# QL_keyboard.net
KiCad netlist of a schematic drawn in EAGLE
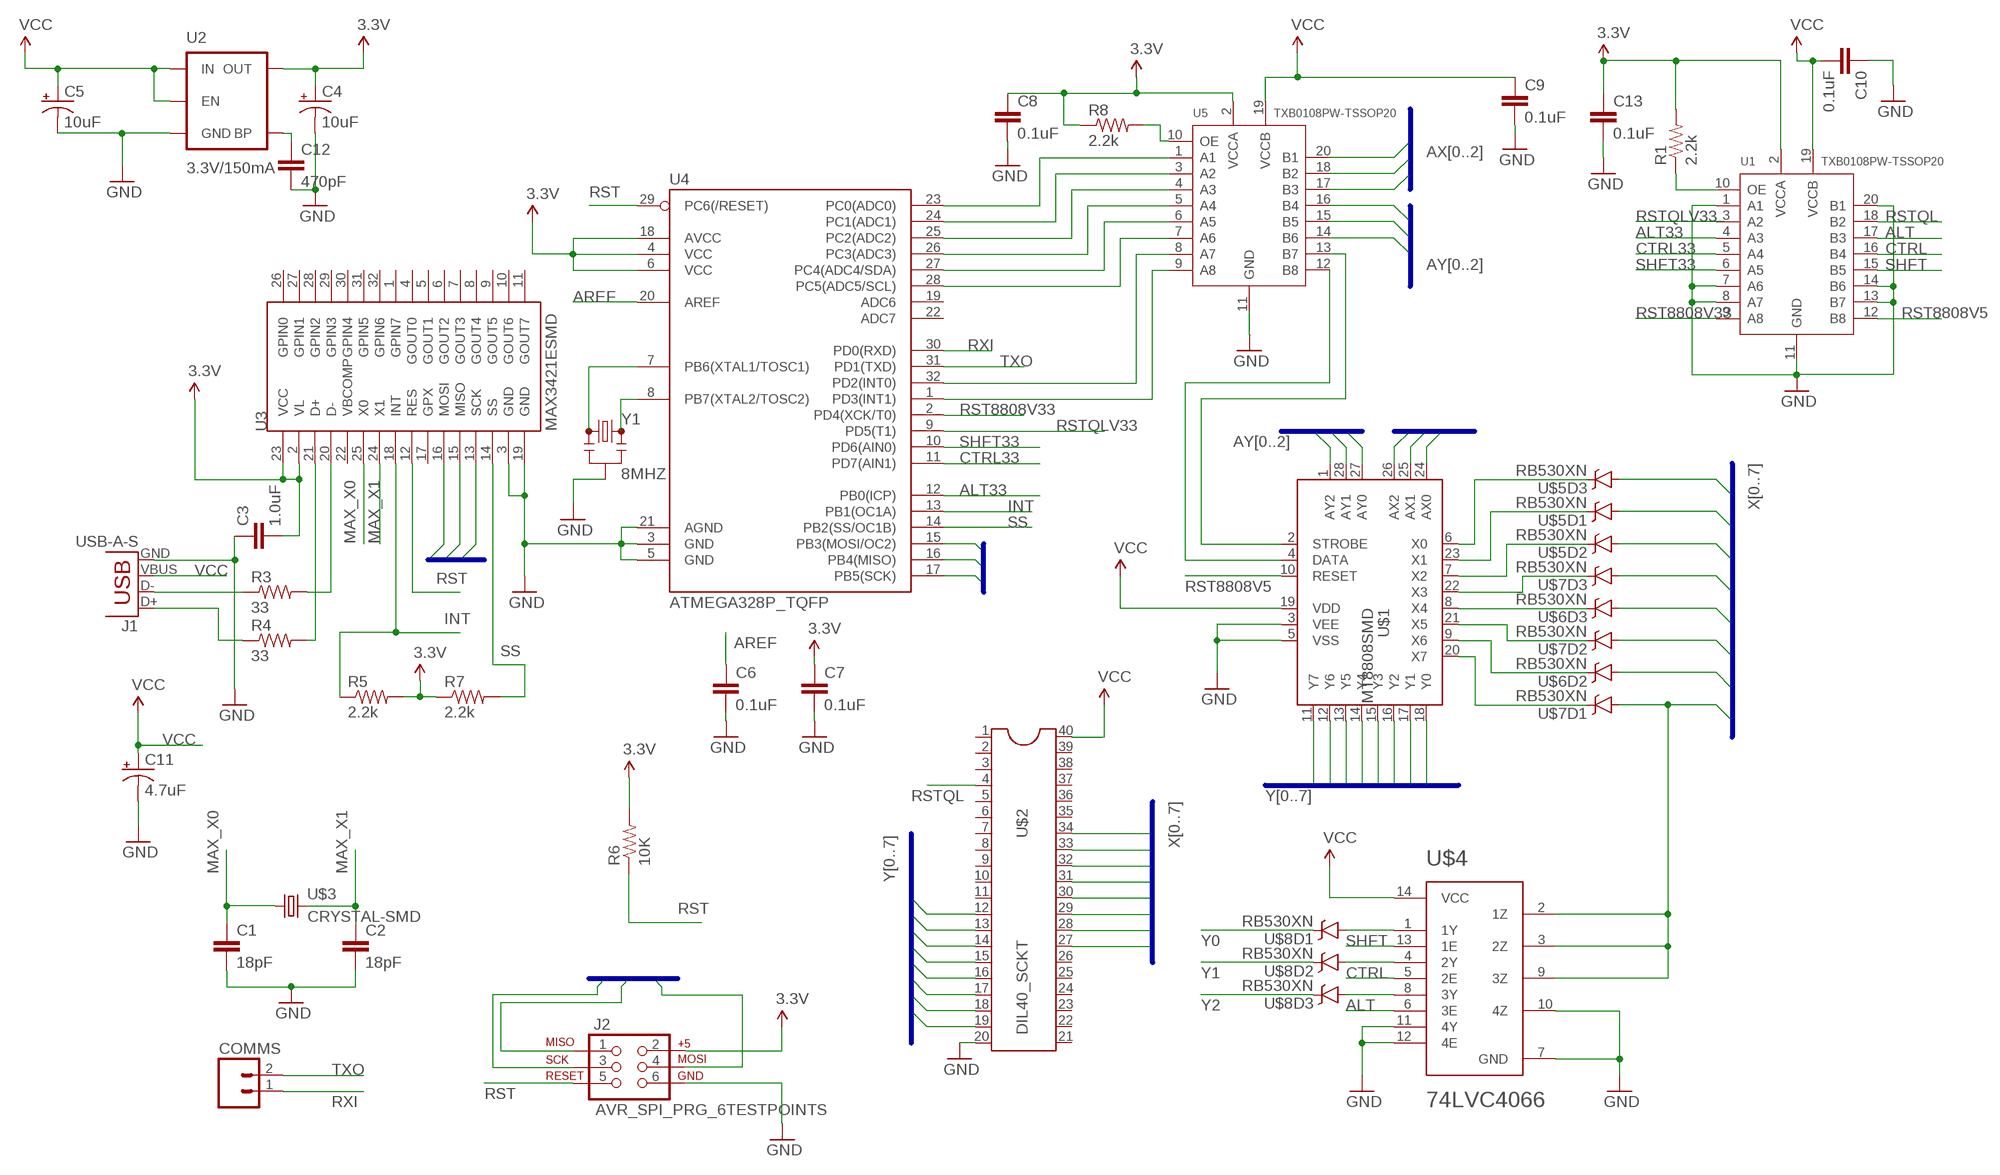
[diagram p0: schematic, sheet 1]

(export (version "E")
  (design (tool "Eeschema 10.0.6"))
  (components
    (comp (ref "C1")
      (value "18pF")
      (footprint "eagle-import:0603-CAP")
      (libsource (lib "eagle-import") (part "CAP0603-CAP"))
    )
    (comp (ref "C2")
      (value "18pF")
      (footprint "eagle-import:0603-CAP")
      (libsource (lib "eagle-import") (part "CAP0603-CAP"))
    )
    (comp (ref "C3")
      (value "1.0uF")
      (footprint "eagle-import:0603-CAP")
      (libsource (lib "eagle-import") (part "1.0UF-16V-10%(0603)"))
    )
    (comp (ref "C4")
      (value "10uF")
      (footprint "eagle-import:EIA3216")
      (libsource (lib "eagle-import") (part "10UF-16V-10%(TANT)"))
    )
    (comp (ref "C5")
      (value "10uF")
      (footprint "eagle-import:EIA3216")
      (libsource (lib "eagle-import") (part "10UF-16V-10%(TANT)"))
    )
    (comp (ref "C6")
      (value "0.1uF")
      (footprint "eagle-import:0603-CAP")
      (libsource (lib "eagle-import") (part "2.2UF-10V-20%(0603)"))
    )
    (comp (ref "C7")
      (value "0.1uF")
      (footprint "eagle-import:0603-CAP")
      (libsource (lib "eagle-import") (part "2.2UF-10V-20%(0603)"))
    )
    (comp (ref "C8")
      (value "0.1uF")
      (footprint "eagle-import:0603-CAP")
      (libsource (lib "eagle-import") (part "2.2UF-10V-20%(0603)"))
    )
    (comp (ref "C9")
      (value "0.1uF")
      (footprint "eagle-import:0603-CAP")
      (libsource (lib "eagle-import") (part "2.2UF-10V-20%(0603)"))
    )
    (comp (ref "C10")
      (value "0.1uF")
      (footprint "eagle-import:0603-CAP")
      (libsource (lib "eagle-import") (part "2.2UF-10V-20%(0603)"))
    )
    (comp (ref "C11")
      (value "4.7uF")
      (footprint "eagle-import:0603-POL")
      (libsource (lib "eagle-import") (part "10UF-6.3V-20%(0603)(TANT){dblquote}"))
    )
    (comp (ref "C12")
      (value "470pF")
      (footprint "eagle-import:0603-CAP")
      (libsource (lib "eagle-import") (part "2.2UF-10V-20%(0603)"))
    )
    (comp (ref "C13")
      (value "0.1uF")
      (footprint "eagle-import:0603-CAP")
      (libsource (lib "eagle-import") (part "2.2UF-10V-20%(0603)"))
    )
    (comp (ref "COMMS")
      (value "M02PTH")
      (footprint "eagle-import:1X02")
      (libsource (lib "eagle-import") (part "M02PTH"))
    )
    (comp (ref "J1")
      (value "USB-A-S")
      (footprint "eagle-import:USB-A-S")
      (libsource (lib "eagle-import") (part "USB-A-S"))
    )
    (comp (ref "J2")
      (value "AVR_SPI_PRG_6TESTPOINTS")
      (footprint "eagle-import:2X3_TEST_POINTS")
      (libsource (lib "eagle-import") (part "AVR_SPI_PRG_6TESTPOINTS"))
    )
    (comp (ref "R1")
      (value "2.2k")
      (footprint "eagle-import:0603-RES")
      (libsource (lib "eagle-import") (part "2.2KOHM-1/10W-1%(0603)"))
    )
    (comp (ref "R3")
      (value "33")
      (footprint "eagle-import:0603-RES")
      (libsource (lib "eagle-import") (part "33OHM1/10W1%(0603)"))
    )
    (comp (ref "R4")
      (value "33")
      (footprint "eagle-import:0603-RES")
      (libsource (lib "eagle-import") (part "33OHM1/10W1%(0603)"))
    )
    (comp (ref "R5")
      (value "2.2k")
      (footprint "eagle-import:0603-RES")
      (libsource (lib "eagle-import") (part "2.2KOHM-1/10W-1%(0603)"))
    )
    (comp (ref "R6")
      (value "10K")
      (footprint "eagle-import:0603-RES")
      (libsource (lib "eagle-import") (part "10KOHM-1/10W-1%(0603)0603"))
    )
    (comp (ref "R7")
      (value "2.2k")
      (footprint "eagle-import:0603-RES")
      (libsource (lib "eagle-import") (part "2.2KOHM-1/10W-1%(0603)"))
    )
    (comp (ref "R8")
      (value "2.2k")
      (footprint "eagle-import:0603-RES")
      (libsource (lib "eagle-import") (part "2.2KOHM-1/10W-1%(0603)"))
    )
    (comp (ref "U$1")
      (value "MT8808SMD")
      (footprint "eagle-import:PLCC28S")
      (libsource (lib "eagle-import") (part "MT8808SMD"))
    )
    (comp (ref "U$2")
      (value "DIL40_SCKT")
      (footprint "eagle-import:DIL40")
      (libsource (lib "eagle-import") (part "DIL40_SCKT"))
    )
    (comp (ref "U$3")
      (value "CRYSTAL-SMD")
      (footprint "eagle-import:CRYSTAL-SMD-5X3.2")
      (libsource (lib "eagle-import") (part "CRYSTAL-SMD"))
    )
    (comp (ref "U$4")
      (value "74LVC4066")
      (footprint "eagle-import:TSSOP14")
      (libsource (lib "eagle-import") (part "74LVC4066"))
    )
    (comp (ref "U$5")
      (value "RB530XN")
      (footprint "eagle-import:SOT363")
      (libsource (lib "eagle-import") (part "RB530XN"))
    )
    (comp (ref "U$6")
      (value "RB530XN")
      (footprint "eagle-import:SOT363")
      (libsource (lib "eagle-import") (part "RB530XN"))
    )
    (comp (ref "U$7")
      (value "RB530XN")
      (footprint "eagle-import:SOT363")
      (libsource (lib "eagle-import") (part "RB530XN"))
    )
    (comp (ref "U$8")
      (value "RB530XN")
      (footprint "eagle-import:SOT363")
      (libsource (lib "eagle-import") (part "RB530XN"))
    )
    (comp (ref "U1")
      (value "TXB0108PW-TSSOP20")
      (footprint "eagle-import:TSSOP20-0.65-6.5X4.4MM")
      (fields (field (name "MPN") "TXB0108PW"))
      (libsource (lib "eagle-import") (part "LOGIC-TXB0108PW(TSSOP20)"))
    )
    (comp (ref "U2")
      (value "3.3V/150mA")
      (footprint "eagle-import:SOT23-5")
      (libsource (lib "eagle-import") (part "V_REG_MIC52053.3V"))
    )
    (comp (ref "U3")
      (value "MAX3421ESMD")
      (footprint "eagle-import:TQFP32-5MM")
      (libsource (lib "eagle-import") (part "MAX3421ESMD"))
    )
    (comp (ref "U4")
      (value "ATMEGA328P_TQFP")
      (footprint "eagle-import:TQFP32-08")
      (libsource (lib "eagle-import") (part "ATMEGA328P_TQFP"))
    )
    (comp (ref "U5")
      (value "TXB0108PW-TSSOP20")
      (footprint "eagle-import:TSSOP20-0.65-6.5X4.4MM")
      (fields (field (name "MPN") "TXB0108PW"))
      (libsource (lib "eagle-import") (part "LOGIC-TXB0108PW(TSSOP20)"))
    )
    (comp (ref "Y1")
      (value "8MHZ")
      (footprint "eagle-import:RESONATOR-SMD")
      (libsource (lib "eagle-import") (part "RESONATOR8MHZ"))
    )
  )
  (nets
    (net (code "1") (name "/ALT") (class "Default")
      (node (ref "U$4") (pin "6") (pinfunction "3E_6") (pintype "input"))
      (node (ref "U1") (pin "17") (pinfunction "B3_17") (pintype "bidirectional"))
    )
    (net (code "2") (name "/ALT33") (class "Default")
      (node (ref "U1") (pin "4") (pinfunction "A3_4") (pintype "bidirectional"))
      (node (ref "U4") (pin "12") (pinfunction "PB0(ICP)_12") (pintype "bidirectional"))
    )
    (net (code "3") (name "/AREF") (class "Default")
      (node (ref "C6") (pin "1") (pinfunction "1_1") (pintype "passive"))
      (node (ref "U4") (pin "20") (pinfunction "AREF_20") (pintype "bidirectional"))
    )
    (net (code "4") (name "/AX0") (class "Default")
      (node (ref "U$1") (pin "24") (pinfunction "AX0_24") (pintype "input"))
      (node (ref "U5") (pin "20") (pinfunction "B1_20") (pintype "bidirectional"))
    )
    (net (code "5") (name "/AX1") (class "Default")
      (node (ref "U$1") (pin "25") (pinfunction "AX1_25") (pintype "input"))
      (node (ref "U5") (pin "18") (pinfunction "B2_18") (pintype "bidirectional"))
    )
    (net (code "6") (name "/AX2") (class "Default")
      (node (ref "U$1") (pin "26") (pinfunction "AX2_26") (pintype "input"))
      (node (ref "U5") (pin "17") (pinfunction "B3_17") (pintype "bidirectional"))
    )
    (net (code "8") (name "/AY0") (class "Default")
      (node (ref "U$1") (pin "27") (pinfunction "AY0_27") (pintype "input"))
      (node (ref "U5") (pin "16") (pinfunction "B4_16") (pintype "bidirectional"))
    )
    (net (code "9") (name "/AY1") (class "Default")
      (node (ref "U$1") (pin "28") (pinfunction "AY1_28") (pintype "input"))
      (node (ref "U5") (pin "15") (pinfunction "B5_15") (pintype "bidirectional"))
    )
    (net (code "10") (name "/AY2") (class "Default")
      (node (ref "U$1") (pin "1") (pinfunction "AY2_1") (pintype "input"))
      (node (ref "U5") (pin "14") (pinfunction "B6_14") (pintype "bidirectional"))
    )
    (net (code "12") (name "/CTRL") (class "Default")
      (node (ref "U$4") (pin "5") (pinfunction "2E_5") (pintype "input"))
      (node (ref "U1") (pin "16") (pinfunction "B4_16") (pintype "bidirectional"))
    )
    (net (code "13") (name "/CTRL33") (class "Default")
      (node (ref "U1") (pin "5") (pinfunction "A4_5") (pintype "bidirectional"))
      (node (ref "U4") (pin "11") (pinfunction "PD7(AIN1)_11") (pintype "bidirectional"))
    )
    (net (code "14") (name "/INT") (class "Default")
      (node (ref "R5") (pin "1") (pinfunction "1_1") (pintype "passive"))
      (node (ref "U3") (pin "18") (pinfunction "INT_18") (pintype "bidirectional"))
      (node (ref "U4") (pin "13") (pinfunction "PB1(OC1A)_13") (pintype "bidirectional"))
    )
    (net (code "15") (name "/MAX_X0") (class "Default")
      (node (ref "C1") (pin "1") (pinfunction "1_1") (pintype "passive"))
      (node (ref "U$3") (pin "1") (pinfunction "1_1") (pintype "passive"))
      (node (ref "U3") (pin "25") (pinfunction "X0_25") (pintype "bidirectional"))
    )
    (net (code "16") (name "/MAX_X1") (class "Default")
      (node (ref "C2") (pin "1") (pinfunction "1_1") (pintype "passive"))
      (node (ref "U$3") (pin "2") (pinfunction "2_2") (pintype "passive"))
      (node (ref "U3") (pin "24") (pinfunction "X1_24") (pintype "bidirectional"))
    )
    (net (code "17") (name "/MISO") (class "Default")
      (node (ref "J2") (pin "1") (pinfunction "1_1") (pintype "passive"))
      (node (ref "U3") (pin "15") (pinfunction "MISO_15") (pintype "bidirectional"))
      (node (ref "U4") (pin "16") (pinfunction "PB4(MISO)_16") (pintype "bidirectional"))
    )
    (net (code "18") (name "/MOSI") (class "Default")
      (node (ref "J2") (pin "4") (pinfunction "4_4") (pintype "passive"))
      (node (ref "U3") (pin "16") (pinfunction "MOSI_16") (pintype "bidirectional"))
      (node (ref "U4") (pin "15") (pinfunction "PB3(MOSI/OC2)_15") (pintype "bidirectional"))
    )
    (net (code "19") (name "/RST") (class "Default")
      (node (ref "J2") (pin "5") (pinfunction "5_5") (pintype "passive"))
      (node (ref "R6") (pin "1") (pinfunction "1_1") (pintype "passive"))
      (node (ref "U3") (pin "12") (pinfunction "RES_12") (pintype "bidirectional"))
      (node (ref "U4") (pin "29") (pinfunction "PC6(/RESET)_29") (pintype "bidirectional"))
    )
    (net (code "20") (name "/RST8808V5") (class "Default")
      (node (ref "U$1") (pin "10") (pinfunction "RESET_10") (pintype "input"))
      (node (ref "U1") (pin "12") (pinfunction "B8_12") (pintype "bidirectional"))
    )
    (net (code "21") (name "/RST8808V33") (class "Default")
      (node (ref "U1") (pin "9") (pinfunction "A8_9") (pintype "bidirectional"))
      (node (ref "U4") (pin "2") (pinfunction "PD4(XCK/T0)_2") (pintype "bidirectional"))
    )
    (net (code "22") (name "/RSTQL") (class "Default")
      (node (ref "U$2") (pin "4") (pinfunction "4_4") (pintype "passive"))
      (node (ref "U1") (pin "18") (pinfunction "B2_18") (pintype "bidirectional"))
    )
    (net (code "23") (name "/RSTQLV33") (class "Default")
      (node (ref "U4") (pin "9") (pinfunction "PD5(T1)_9") (pintype "bidirectional"))
    )
    (net (code "24") (name "/RXI") (class "Default")
      (node (ref "COMMS") (pin "1") (pinfunction "1_1") (pintype "passive"))
      (node (ref "U4") (pin "30") (pinfunction "PD0(RXD)_30") (pintype "bidirectional"))
    )
    (net (code "25") (name "/SCK") (class "Default")
      (node (ref "J2") (pin "3") (pinfunction "3_3") (pintype "passive"))
      (node (ref "U3") (pin "13") (pinfunction "SCK_13") (pintype "bidirectional"))
      (node (ref "U4") (pin "17") (pinfunction "PB5(SCK)_17") (pintype "bidirectional"))
    )
    (net (code "26") (name "/SHFT") (class "Default")
      (node (ref "U$4") (pin "13") (pinfunction "1E_13") (pintype "input"))
      (node (ref "U1") (pin "15") (pinfunction "B5_15") (pintype "bidirectional"))
    )
    (net (code "27") (name "/SHFT33") (class "Default")
      (node (ref "U1") (pin "6") (pinfunction "A5_6") (pintype "bidirectional"))
      (node (ref "U4") (pin "10") (pinfunction "PD6(AIN0)_10") (pintype "bidirectional"))
    )
    (net (code "28") (name "/SS") (class "Default")
      (node (ref "R7") (pin "2") (pinfunction "2_2") (pintype "passive"))
      (node (ref "U3") (pin "14") (pinfunction "SS_14") (pintype "bidirectional"))
      (node (ref "U4") (pin "14") (pinfunction "PB2(SS/OC1B)_14") (pintype "bidirectional"))
    )
    (net (code "29") (name "/TXO") (class "Default")
      (node (ref "COMMS") (pin "2") (pinfunction "2_2") (pintype "passive"))
      (node (ref "U4") (pin "31") (pinfunction "PD1(TXD)_31") (pintype "bidirectional"))
    )
    (net (code "30") (name "/X0") (class "Default")
      (node (ref "U$2") (pin "27") (pinfunction "27_27") (pintype "passive"))
      (node (ref "U$5") (pin "4") (pinfunction "A_4") (pintype "passive"))
    )
    (net (code "31") (name "/X1") (class "Default")
      (node (ref "U$2") (pin "28") (pinfunction "28_28") (pintype "passive"))
      (node (ref "U$5") (pin "6") (pinfunction "A_6") (pintype "passive"))
    )
    (net (code "32") (name "/X2") (class "Default")
      (node (ref "U$2") (pin "29") (pinfunction "29_29") (pintype "passive"))
      (node (ref "U$5") (pin "5") (pinfunction "A_5") (pintype "passive"))
    )
    (net (code "33") (name "/X3") (class "Default")
      (node (ref "U$2") (pin "30") (pinfunction "30_30") (pintype "passive"))
      (node (ref "U$7") (pin "4") (pinfunction "A_4") (pintype "passive"))
    )
    (net (code "34") (name "/X4") (class "Default")
      (node (ref "U$2") (pin "31") (pinfunction "31_31") (pintype "passive"))
      (node (ref "U$6") (pin "4") (pinfunction "A_4") (pintype "passive"))
    )
    (net (code "35") (name "/X5") (class "Default")
      (node (ref "U$2") (pin "32") (pinfunction "32_32") (pintype "passive"))
      (node (ref "U$7") (pin "5") (pinfunction "A_5") (pintype "passive"))
    )
    (net (code "36") (name "/X6") (class "Default")
      (node (ref "U$2") (pin "33") (pinfunction "33_33") (pintype "passive"))
      (node (ref "U$6") (pin "5") (pinfunction "A_5") (pintype "passive"))
    )
    (net (code "37") (name "/X7") (class "Default")
      (node (ref "U$2") (pin "34") (pinfunction "34_34") (pintype "passive"))
      (node (ref "U$4") (pin "2") (pinfunction "1Z_2") (pintype "bidirectional"))
      (node (ref "U$4") (pin "3") (pinfunction "2Z_3") (pintype "bidirectional"))
      (node (ref "U$4") (pin "9") (pinfunction "3Z_9") (pintype "bidirectional"))
      (node (ref "U$7") (pin "6") (pinfunction "A_6") (pintype "passive"))
    )
    (net (code "39") (name "/Y0") (class "Default")
      (node (ref "U$1") (pin "18") (pinfunction "Y0_18") (pintype "bidirectional"))
      (node (ref "U$2") (pin "12") (pinfunction "12_12") (pintype "passive"))
      (node (ref "U$8") (pin "1") (pinfunction "C_1") (pintype "passive"))
    )
    (net (code "40") (name "/Y1") (class "Default")
      (node (ref "U$1") (pin "17") (pinfunction "Y1_17") (pintype "bidirectional"))
      (node (ref "U$2") (pin "13") (pinfunction "13_13") (pintype "passive"))
      (node (ref "U$8") (pin "2") (pinfunction "C_2") (pintype "passive"))
    )
    (net (code "41") (name "/Y2") (class "Default")
      (node (ref "U$1") (pin "16") (pinfunction "Y2_16") (pintype "bidirectional"))
      (node (ref "U$2") (pin "14") (pinfunction "14_14") (pintype "passive"))
      (node (ref "U$8") (pin "3") (pinfunction "C_3") (pintype "passive"))
    )
    (net (code "42") (name "/Y3") (class "Default")
      (node (ref "U$1") (pin "15") (pinfunction "Y3_15") (pintype "bidirectional"))
      (node (ref "U$2") (pin "15") (pinfunction "15_15") (pintype "passive"))
    )
    (net (code "43") (name "/Y4") (class "Default")
      (node (ref "U$1") (pin "14") (pinfunction "Y4_14") (pintype "bidirectional"))
      (node (ref "U$2") (pin "16") (pinfunction "16_16") (pintype "passive"))
    )
    (net (code "44") (name "/Y5") (class "Default")
      (node (ref "U$1") (pin "13") (pinfunction "Y5_13") (pintype "bidirectional"))
      (node (ref "U$2") (pin "17") (pinfunction "17_17") (pintype "passive"))
    )
    (net (code "45") (name "/Y6") (class "Default")
      (node (ref "U$1") (pin "12") (pinfunction "Y6_12") (pintype "bidirectional"))
      (node (ref "U$2") (pin "18") (pinfunction "18_18") (pintype "passive"))
    )
    (net (code "46") (name "/Y7") (class "Default")
      (node (ref "U$1") (pin "11") (pinfunction "Y7_11") (pintype "bidirectional"))
      (node (ref "U$2") (pin "19") (pinfunction "19_19") (pintype "passive"))
    )
    (net (code "49") (name "3.3V") (class "Default")
      (node (ref "C13") (pin "1") (pinfunction "1_1") (pintype "passive"))
      (node (ref "C3") (pin "2") (pinfunction "2_2") (pintype "passive"))
      (node (ref "C4") (pin "A") (pinfunction "+_A") (pintype "passive"))
      (node (ref "C7") (pin "1") (pinfunction "1_1") (pintype "passive"))
      (node (ref "C8") (pin "1") (pinfunction "1_1") (pintype "passive"))
      (node (ref "J2") (pin "2") (pinfunction "2_2") (pintype "passive"))
      (node (ref "R1") (pin "2") (pinfunction "2_2") (pintype "passive"))
      (node (ref "R5") (pin "2") (pinfunction "2_2") (pintype "passive"))
      (node (ref "R6") (pin "2") (pinfunction "2_2") (pintype "passive"))
      (node (ref "R7") (pin "1") (pinfunction "1_1") (pintype "passive"))
      (node (ref "R8") (pin "1") (pinfunction "1_1") (pintype "passive"))
      (node (ref "U1") (pin "2") (pinfunction "VCCA_2") (pintype "bidirectional"))
      (node (ref "U2") (pin "5") (pinfunction "OUT_5") (pintype "passive"))
      (node (ref "U3") (pin "2") (pinfunction "VL_2") (pintype "bidirectional"))
      (node (ref "U3") (pin "23") (pinfunction "VCC_23") (pintype "bidirectional"))
      (node (ref "U4") (pin "18") (pinfunction "AVCC_18") (pintype "bidirectional"))
      (node (ref "U4") (pin "4") (pinfunction "VCC_4") (pintype "bidirectional"))
      (node (ref "U4") (pin "6") (pinfunction "VCC_6") (pintype "bidirectional"))
      (node (ref "U5") (pin "2") (pinfunction "VCCA_2") (pintype "bidirectional"))
    )
    (net (code "50") (name "GND") (class "Default")
      (node (ref "C1") (pin "2") (pinfunction "2_2") (pintype "passive"))
      (node (ref "C10") (pin "1") (pinfunction "1_1") (pintype "passive"))
      (node (ref "C11") (pin "K") (pinfunction "-_K") (pintype "passive"))
      (node (ref "C12") (pin "2") (pinfunction "2_2") (pintype "passive"))
      (node (ref "C13") (pin "2") (pinfunction "2_2") (pintype "passive"))
      (node (ref "C2") (pin "2") (pinfunction "2_2") (pintype "passive"))
      (node (ref "C3") (pin "1") (pinfunction "1_1") (pintype "passive"))
      (node (ref "C4") (pin "C") (pinfunction "-_C") (pintype "passive"))
      (node (ref "C5") (pin "C") (pinfunction "-_C") (pintype "passive"))
      (node (ref "C6") (pin "2") (pinfunction "2_2") (pintype "passive"))
      (node (ref "C7") (pin "2") (pinfunction "2_2") (pintype "passive"))
      (node (ref "C8") (pin "2") (pinfunction "2_2") (pintype "passive"))
      (node (ref "C9") (pin "2") (pinfunction "2_2") (pintype "passive"))
      (node (ref "J1") (pin "GND") (pinfunction "GND_GND") (pintype "bidirectional"))
      (node (ref "J2") (pin "6") (pinfunction "6_6") (pintype "passive"))
      (node (ref "U$1") (pin "3") (pinfunction "VEE_3") (pintype "power_in"))
      (node (ref "U$1") (pin "5") (pinfunction "VSS_5") (pintype "power_in"))
      (node (ref "U$2") (pin "20") (pinfunction "20_20") (pintype "passive"))
      (node (ref "U$4") (pin "10") (pinfunction "4Z_10") (pintype "bidirectional"))
      (node (ref "U$4") (pin "11") (pinfunction "4Y_11") (pintype "input"))
      (node (ref "U$4") (pin "12") (pinfunction "4E_12") (pintype "bidirectional"))
      (node (ref "U$4") (pin "7") (pinfunction "GND_7") (pintype "bidirectional"))
      (node (ref "U1") (pin "1") (pinfunction "A1_1") (pintype "bidirectional"))
      (node (ref "U1") (pin "11") (pinfunction "GND_11") (pintype "bidirectional"))
      (node (ref "U1") (pin "13") (pinfunction "B7_13") (pintype "bidirectional"))
      (node (ref "U1") (pin "14") (pinfunction "B6_14") (pintype "bidirectional"))
      (node (ref "U1") (pin "20") (pinfunction "B1_20") (pintype "bidirectional"))
      (node (ref "U1") (pin "7") (pinfunction "A6_7") (pintype "bidirectional"))
      (node (ref "U1") (pin "8") (pinfunction "A7_8") (pintype "bidirectional"))
      (node (ref "U2") (pin "2") (pinfunction "GND_2") (pintype "input"))
      (node (ref "U3") (pin "19") (pinfunction "GND_19") (pintype "bidirectional"))
      (node (ref "U3") (pin "3") (pinfunction "GND_3") (pintype "bidirectional"))
      (node (ref "U4") (pin "21") (pinfunction "AGND_21") (pintype "bidirectional"))
      (node (ref "U4") (pin "3") (pinfunction "GND_3") (pintype "bidirectional"))
      (node (ref "U4") (pin "5") (pinfunction "GND_5") (pintype "bidirectional"))
      (node (ref "U5") (pin "11") (pinfunction "GND_11") (pintype "bidirectional"))
      (node (ref "Y1") (pin "2") (pinfunction "2_2") (pintype "passive"))
    )
    (net (code "51") (name "Net-(J1-PadD+)") (class "Default")
      (node (ref "J1") (pin "D+") (pinfunction "D+_D+") (pintype "bidirectional"))
      (node (ref "R4") (pin "1") (pinfunction "1_1") (pintype "passive"))
    )
    (net (code "52") (name "Net-(J1-PadD-)") (class "Default")
      (node (ref "J1") (pin "D-") (pinfunction "D-_D-") (pintype "bidirectional"))
      (node (ref "R3") (pin "1") (pinfunction "1_1") (pintype "passive"))
    )
    (net (code "53") (name "Net-(U$1-DATA)") (class "Default")
      (node (ref "U$1") (pin "4") (pinfunction "DATA_4") (pintype "input"))
      (node (ref "U5") (pin "12") (pinfunction "B8_12") (pintype "bidirectional"))
    )
    (net (code "54") (name "Net-(U$1-STROBE)") (class "Default")
      (node (ref "U$1") (pin "2") (pinfunction "STROBE_2") (pintype "input"))
      (node (ref "U5") (pin "13") (pinfunction "B7_13") (pintype "bidirectional"))
    )
    (net (code "55") (name "Net-(U$1-X0)") (class "Default")
      (node (ref "U$1") (pin "6") (pinfunction "X0_6") (pintype "bidirectional"))
      (node (ref "U$5") (pin "3") (pinfunction "C_3") (pintype "passive"))
    )
    (net (code "56") (name "Net-(U$1-X1)") (class "Default")
      (node (ref "U$1") (pin "23") (pinfunction "X1_23") (pintype "bidirectional"))
      (node (ref "U$5") (pin "1") (pinfunction "C_1") (pintype "passive"))
    )
    (net (code "57") (name "Net-(U$1-X2)") (class "Default")
      (node (ref "U$1") (pin "7") (pinfunction "X2_7") (pintype "bidirectional"))
      (node (ref "U$5") (pin "2") (pinfunction "C_2") (pintype "passive"))
    )
    (net (code "58") (name "Net-(U$1-X3)") (class "Default")
      (node (ref "U$1") (pin "22") (pinfunction "X3_22") (pintype "bidirectional"))
      (node (ref "U$7") (pin "3") (pinfunction "C_3") (pintype "passive"))
    )
    (net (code "59") (name "Net-(U$1-X4)") (class "Default")
      (node (ref "U$1") (pin "8") (pinfunction "X4_8") (pintype "bidirectional"))
      (node (ref "U$6") (pin "3") (pinfunction "C_3") (pintype "passive"))
    )
    (net (code "60") (name "Net-(U$1-X5)") (class "Default")
      (node (ref "U$1") (pin "21") (pinfunction "X5_21") (pintype "bidirectional"))
      (node (ref "U$7") (pin "2") (pinfunction "C_2") (pintype "passive"))
    )
    (net (code "61") (name "Net-(U$1-X6)") (class "Default")
      (node (ref "U$1") (pin "9") (pinfunction "X6_9") (pintype "bidirectional"))
      (node (ref "U$6") (pin "2") (pinfunction "C_2") (pintype "passive"))
    )
    (net (code "62") (name "Net-(U$1-X7)") (class "Default")
      (node (ref "U$1") (pin "20") (pinfunction "X7_20") (pintype "bidirectional"))
      (node (ref "U$7") (pin "1") (pinfunction "C_1") (pintype "passive"))
    )
    (net (code "63") (name "Net-(U$4-1Y)") (class "Default")
      (node (ref "U$4") (pin "1") (pinfunction "1Y_1") (pintype "bidirectional"))
      (node (ref "U$8") (pin "6") (pinfunction "A_6") (pintype "passive"))
    )
    (net (code "64") (name "Net-(U$4-2Y)") (class "Default")
      (node (ref "U$4") (pin "4") (pinfunction "2Y_4") (pintype "bidirectional"))
      (node (ref "U$8") (pin "5") (pinfunction "A_5") (pintype "passive"))
    )
    (net (code "65") (name "Net-(U$4-3Y)") (class "Default")
      (node (ref "U$4") (pin "8") (pinfunction "3Y_8") (pintype "bidirectional"))
      (node (ref "U$8") (pin "4") (pinfunction "A_4") (pintype "passive"))
    )
    (net (code "66") (name "Net-(U1-OE)") (class "Default")
      (node (ref "R1") (pin "1") (pinfunction "1_1") (pintype "passive"))
      (node (ref "U1") (pin "10") (pinfunction "OE_10") (pintype "bidirectional"))
    )
    (net (code "67") (name "Net-(U2-BP)") (class "Default")
      (node (ref "C12") (pin "1") (pinfunction "1_1") (pintype "passive"))
      (node (ref "U2") (pin "4") (pinfunction "BP_4") (pintype "input"))
    )
    (net (code "68") (name "Net-(U3-D+)") (class "Default")
      (node (ref "R4") (pin "2") (pinfunction "2_2") (pintype "passive"))
      (node (ref "U3") (pin "21") (pinfunction "D+_21") (pintype "bidirectional"))
    )
    (net (code "69") (name "Net-(U3-D-)") (class "Default")
      (node (ref "R3") (pin "2") (pinfunction "2_2") (pintype "passive"))
      (node (ref "U3") (pin "20") (pinfunction "D-_20") (pintype "bidirectional"))
    )
    (net (code "70") (name "Net-(U4-PB6(XTAL1{slash}TOSC1))") (class "Default")
      (node (ref "U4") (pin "7") (pinfunction "PB6(XTAL1/TOSC1)_7") (pintype "bidirectional"))
      (node (ref "Y1") (pin "1") (pinfunction "1_1") (pintype "passive"))
    )
    (net (code "71") (name "Net-(U4-PB7(XTAL2{slash}TOSC2))") (class "Default")
      (node (ref "U4") (pin "8") (pinfunction "PB7(XTAL2/TOSC2)_8") (pintype "bidirectional"))
      (node (ref "Y1") (pin "3") (pinfunction "3_3") (pintype "passive"))
    )
    (net (code "72") (name "Net-(U4-PC0(ADC0))") (class "Default")
      (node (ref "U4") (pin "23") (pinfunction "PC0(ADC0)_23") (pintype "bidirectional"))
      (node (ref "U5") (pin "1") (pinfunction "A1_1") (pintype "bidirectional"))
    )
    (net (code "73") (name "Net-(U4-PC1(ADC1))") (class "Default")
      (node (ref "U4") (pin "24") (pinfunction "PC1(ADC1)_24") (pintype "bidirectional"))
      (node (ref "U5") (pin "3") (pinfunction "A2_3") (pintype "bidirectional"))
    )
    (net (code "74") (name "Net-(U4-PC2(ADC2))") (class "Default")
      (node (ref "U4") (pin "25") (pinfunction "PC2(ADC2)_25") (pintype "bidirectional"))
      (node (ref "U5") (pin "4") (pinfunction "A3_4") (pintype "bidirectional"))
    )
    (net (code "75") (name "Net-(U4-PC3(ADC3))") (class "Default")
      (node (ref "U4") (pin "26") (pinfunction "PC3(ADC3)_26") (pintype "bidirectional"))
      (node (ref "U5") (pin "5") (pinfunction "A4_5") (pintype "bidirectional"))
    )
    (net (code "76") (name "Net-(U4-PC4(ADC4{slash}SDA))") (class "Default")
      (node (ref "U4") (pin "27") (pinfunction "PC4(ADC4/SDA)_27") (pintype "bidirectional"))
      (node (ref "U5") (pin "6") (pinfunction "A5_6") (pintype "bidirectional"))
    )
    (net (code "77") (name "Net-(U4-PC5(ADC5{slash}SCL))") (class "Default")
      (node (ref "U4") (pin "28") (pinfunction "PC5(ADC5/SCL)_28") (pintype "bidirectional"))
      (node (ref "U5") (pin "7") (pinfunction "A6_7") (pintype "bidirectional"))
    )
    (net (code "78") (name "Net-(U4-PD2(INT0))") (class "Default")
      (node (ref "U4") (pin "32") (pinfunction "PD2(INT0)_32") (pintype "bidirectional"))
      (node (ref "U5") (pin "8") (pinfunction "A7_8") (pintype "bidirectional"))
    )
    (net (code "79") (name "Net-(U4-PD3(INT1))") (class "Default")
      (node (ref "U4") (pin "1") (pinfunction "PD3(INT1)_1") (pintype "bidirectional"))
      (node (ref "U5") (pin "9") (pinfunction "A8_9") (pintype "bidirectional"))
    )
    (net (code "80") (name "Net-(U5-OE)") (class "Default")
      (node (ref "R8") (pin "2") (pinfunction "2_2") (pintype "passive"))
      (node (ref "U5") (pin "10") (pinfunction "OE_10") (pintype "bidirectional"))
    )
    (net (code "81") (name "VCC") (class "Default")
      (node (ref "C10") (pin "2") (pinfunction "2_2") (pintype "passive"))
      (node (ref "C11") (pin "A") (pinfunction "+_A") (pintype "passive"))
      (node (ref "C5") (pin "A") (pinfunction "+_A") (pintype "passive"))
      (node (ref "C9") (pin "1") (pinfunction "1_1") (pintype "passive"))
      (node (ref "J1") (pin "VBUS") (pinfunction "VBUS_VBUS") (pintype "bidirectional"))
      (node (ref "U$1") (pin "19") (pinfunction "VDD_19") (pintype "power_in"))
      (node (ref "U$2") (pin "40") (pinfunction "40_40") (pintype "passive"))
      (node (ref "U$4") (pin "14") (pinfunction "VCC_14") (pintype "bidirectional"))
      (node (ref "U1") (pin "19") (pinfunction "VCCB_19") (pintype "bidirectional"))
      (node (ref "U2") (pin "1") (pinfunction "IN_1") (pintype "input"))
      (node (ref "U2") (pin "3") (pinfunction "EN_3") (pintype "input"))
      (node (ref "U5") (pin "19") (pinfunction "VCCB_19") (pintype "bidirectional"))
    )
    (net (code "82") (name "unconnected-(U$2-Pad1)") (class "Default")
      (node (ref "U$2") (pin "1") (pinfunction "1_1") (pintype "passive"))
    )
    (net (code "83") (name "unconnected-(U$2-Pad2)") (class "Default")
      (node (ref "U$2") (pin "2") (pinfunction "2_2") (pintype "passive"))
    )
    (net (code "84") (name "unconnected-(U$2-Pad3)") (class "Default")
      (node (ref "U$2") (pin "3") (pinfunction "3_3") (pintype "passive"))
    )
    (net (code "85") (name "unconnected-(U$2-Pad5)") (class "Default")
      (node (ref "U$2") (pin "5") (pinfunction "5_5") (pintype "passive"))
    )
    (net (code "86") (name "unconnected-(U$2-Pad6)") (class "Default")
      (node (ref "U$2") (pin "6") (pinfunction "6_6") (pintype "passive"))
    )
    (net (code "87") (name "unconnected-(U$2-Pad7)") (class "Default")
      (node (ref "U$2") (pin "7") (pinfunction "7_7") (pintype "passive"))
    )
    (net (code "88") (name "unconnected-(U$2-Pad8)") (class "Default")
      (node (ref "U$2") (pin "8") (pinfunction "8_8") (pintype "passive"))
    )
    (net (code "89") (name "unconnected-(U$2-Pad9)") (class "Default")
      (node (ref "U$2") (pin "9") (pinfunction "9_9") (pintype "passive"))
    )
    (net (code "90") (name "unconnected-(U$2-Pad10)") (class "Default")
      (node (ref "U$2") (pin "10") (pinfunction "10_10") (pintype "passive"))
    )
    (net (code "91") (name "unconnected-(U$2-Pad11)") (class "Default")
      (node (ref "U$2") (pin "11") (pinfunction "11_11") (pintype "passive"))
    )
    (net (code "92") (name "unconnected-(U$2-Pad21)") (class "Default")
      (node (ref "U$2") (pin "21") (pinfunction "21_21") (pintype "passive"))
    )
    (net (code "93") (name "unconnected-(U$2-Pad22)") (class "Default")
      (node (ref "U$2") (pin "22") (pinfunction "22_22") (pintype "passive"))
    )
    (net (code "94") (name "unconnected-(U$2-Pad23)") (class "Default")
      (node (ref "U$2") (pin "23") (pinfunction "23_23") (pintype "passive"))
    )
    (net (code "95") (name "unconnected-(U$2-Pad24)") (class "Default")
      (node (ref "U$2") (pin "24") (pinfunction "24_24") (pintype "passive"))
    )
    (net (code "96") (name "unconnected-(U$2-Pad25)") (class "Default")
      (node (ref "U$2") (pin "25") (pinfunction "25_25") (pintype "passive"))
    )
    (net (code "97") (name "unconnected-(U$2-Pad26)") (class "Default")
      (node (ref "U$2") (pin "26") (pinfunction "26_26") (pintype "passive"))
    )
    (net (code "98") (name "unconnected-(U$2-Pad35)") (class "Default")
      (node (ref "U$2") (pin "35") (pinfunction "35_35") (pintype "passive"))
    )
    (net (code "99") (name "unconnected-(U$2-Pad36)") (class "Default")
      (node (ref "U$2") (pin "36") (pinfunction "36_36") (pintype "passive"))
    )
    (net (code "100") (name "unconnected-(U$2-Pad37)") (class "Default")
      (node (ref "U$2") (pin "37") (pinfunction "37_37") (pintype "passive"))
    )
    (net (code "101") (name "unconnected-(U$2-Pad38)") (class "Default")
      (node (ref "U$2") (pin "38") (pinfunction "38_38") (pintype "passive"))
    )
    (net (code "102") (name "unconnected-(U$2-Pad39)") (class "Default")
      (node (ref "U$2") (pin "39") (pinfunction "39_39") (pintype "passive"))
    )
    (net (code "103") (name "unconnected-(U1-A2-Pad3)") (class "Default")
      (node (ref "U1") (pin "3") (pinfunction "A2_3") (pintype "bidirectional"))
    )
    (net (code "104") (name "unconnected-(U3-GOUT0-Pad4)") (class "Default")
      (node (ref "U3") (pin "4") (pinfunction "GOUT0_4") (pintype "bidirectional"))
    )
    (net (code "105") (name "unconnected-(U3-GOUT1-Pad5)") (class "Default")
      (node (ref "U3") (pin "5") (pinfunction "GOUT1_5") (pintype "bidirectional"))
    )
    (net (code "106") (name "unconnected-(U3-GOUT2-Pad6)") (class "Default")
      (node (ref "U3") (pin "6") (pinfunction "GOUT2_6") (pintype "bidirectional"))
    )
    (net (code "107") (name "unconnected-(U3-GOUT3-Pad7)") (class "Default")
      (node (ref "U3") (pin "7") (pinfunction "GOUT3_7") (pintype "bidirectional"))
    )
    (net (code "108") (name "unconnected-(U3-GOUT4-Pad8)") (class "Default")
      (node (ref "U3") (pin "8") (pinfunction "GOUT4_8") (pintype "bidirectional"))
    )
    (net (code "109") (name "unconnected-(U3-GOUT5-Pad9)") (class "Default")
      (node (ref "U3") (pin "9") (pinfunction "GOUT5_9") (pintype "bidirectional"))
    )
    (net (code "110") (name "unconnected-(U3-GOUT6-Pad10)") (class "Default")
      (node (ref "U3") (pin "10") (pinfunction "GOUT6_10") (pintype "bidirectional"))
    )
    (net (code "111") (name "unconnected-(U3-GOUT7-Pad11)") (class "Default")
      (node (ref "U3") (pin "11") (pinfunction "GOUT7_11") (pintype "bidirectional"))
    )
    (net (code "112") (name "unconnected-(U3-GPIN0-Pad26)") (class "Default")
      (node (ref "U3") (pin "26") (pinfunction "GPIN0_26") (pintype "bidirectional"))
    )
    (net (code "113") (name "unconnected-(U3-GPIN1-Pad27)") (class "Default")
      (node (ref "U3") (pin "27") (pinfunction "GPIN1_27") (pintype "bidirectional"))
    )
    (net (code "114") (name "unconnected-(U3-GPIN2-Pad28)") (class "Default")
      (node (ref "U3") (pin "28") (pinfunction "GPIN2_28") (pintype "bidirectional"))
    )
    (net (code "115") (name "unconnected-(U3-GPIN3-Pad29)") (class "Default")
      (node (ref "U3") (pin "29") (pinfunction "GPIN3_29") (pintype "bidirectional"))
    )
    (net (code "116") (name "unconnected-(U3-GPIN4-Pad30)") (class "Default")
      (node (ref "U3") (pin "30") (pinfunction "GPIN4_30") (pintype "bidirectional"))
    )
    (net (code "117") (name "unconnected-(U3-GPIN5-Pad31)") (class "Default")
      (node (ref "U3") (pin "31") (pinfunction "GPIN5_31") (pintype "bidirectional"))
    )
    (net (code "118") (name "unconnected-(U3-GPIN6-Pad32)") (class "Default")
      (node (ref "U3") (pin "32") (pinfunction "GPIN6_32") (pintype "bidirectional"))
    )
    (net (code "119") (name "unconnected-(U3-GPIN7-Pad1)") (class "Default")
      (node (ref "U3") (pin "1") (pinfunction "GPIN7_1") (pintype "bidirectional"))
    )
    (net (code "120") (name "unconnected-(U3-GPX-Pad17)") (class "Default")
      (node (ref "U3") (pin "17") (pinfunction "GPX_17") (pintype "bidirectional"))
    )
    (net (code "121") (name "unconnected-(U3-VBCOMP-Pad22)") (class "Default")
      (node (ref "U3") (pin "22") (pinfunction "VBCOMP_22") (pintype "bidirectional"))
    )
    (net (code "122") (name "unconnected-(U4-ADC6-Pad19)") (class "Default")
      (node (ref "U4") (pin "19") (pinfunction "ADC6_19") (pintype "bidirectional"))
    )
    (net (code "123") (name "unconnected-(U4-ADC7-Pad22)") (class "Default")
      (node (ref "U4") (pin "22") (pinfunction "ADC7_22") (pintype "bidirectional"))
    )
  )
)
